# LOA_Legba.net
KiCad netlist of a schematic drawn in EAGLE
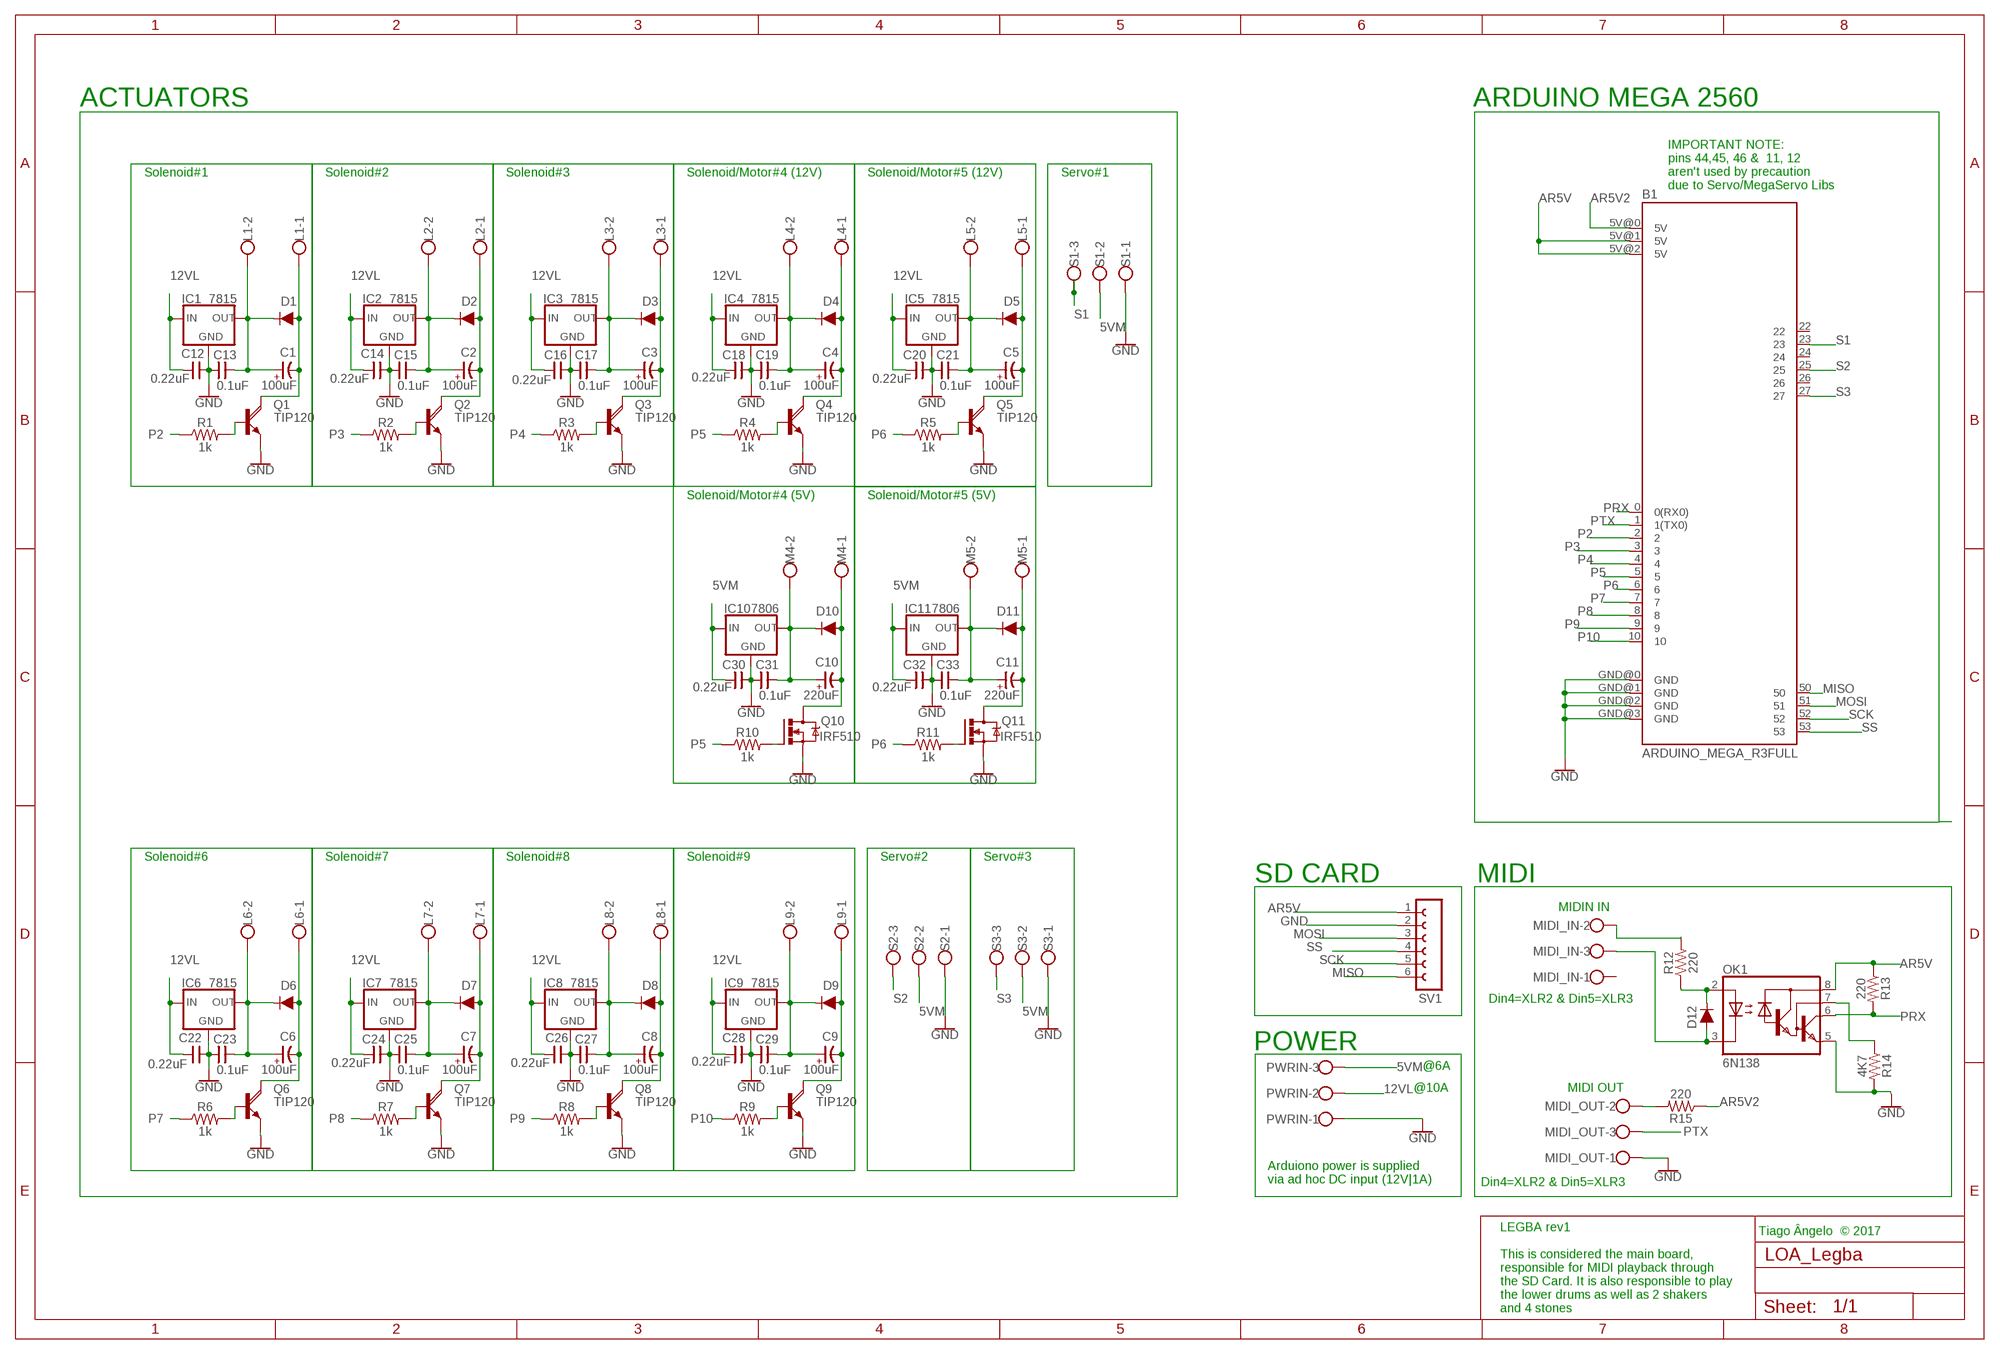
[diagram p0: schematic, sheet 1]

(export (version "E")
  (design (tool "Eeschema 10.0.6"))
  (components
    (comp (ref "B1")
      (value "ARDUINO_MEGA_R3FULL")
      (footprint "eagle-import:ARDUINO_MEGA")
      (libsource (lib "eagle-import") (part "ARDUINO_MEGA_R3FULL"))
    )
    (comp (ref "C1")
      (value "100uF")
      (footprint "eagle-import:CAP-MASTER_E-020X050")
      (libsource (lib "eagle-import") (part "CAP-MASTER_CP-E-020X050"))
    )
    (comp (ref "C2")
      (value "100uF")
      (footprint "eagle-import:CAP-MASTER_E-020X050")
      (libsource (lib "eagle-import") (part "CAP-MASTER_CP-E-020X050"))
    )
    (comp (ref "C3")
      (value "100uF")
      (footprint "eagle-import:CAP-MASTER_E-020X050")
      (libsource (lib "eagle-import") (part "CAP-MASTER_CP-E-020X050"))
    )
    (comp (ref "C4")
      (value "100uF")
      (footprint "eagle-import:CAP-MASTER_E-020X050")
      (libsource (lib "eagle-import") (part "CAP-MASTER_CP-E-020X050"))
    )
    (comp (ref "C5")
      (value "100uF")
      (footprint "eagle-import:CAP-MASTER_E-020X050")
      (libsource (lib "eagle-import") (part "CAP-MASTER_CP-E-020X050"))
    )
    (comp (ref "C6")
      (value "100uF")
      (footprint "eagle-import:CAP-MASTER_E-020X050")
      (libsource (lib "eagle-import") (part "CAP-MASTER_CP-E-020X050"))
    )
    (comp (ref "C7")
      (value "100uF")
      (footprint "eagle-import:CAP-MASTER_E-020X050")
      (libsource (lib "eagle-import") (part "CAP-MASTER_CP-E-020X050"))
    )
    (comp (ref "C8")
      (value "100uF")
      (footprint "eagle-import:CAP-MASTER_E-020X050")
      (libsource (lib "eagle-import") (part "CAP-MASTER_CP-E-020X050"))
    )
    (comp (ref "C9")
      (value "100uF")
      (footprint "eagle-import:CAP-MASTER_E-020X050")
      (libsource (lib "eagle-import") (part "CAP-MASTER_CP-E-020X050"))
    )
    (comp (ref "C10")
      (value "220uF")
      (footprint "eagle-import:E-035X080")
      (libsource (lib "eagle-import") (part "CP-E-035X080"))
    )
    (comp (ref "C11")
      (value "220uF")
      (footprint "eagle-import:E-035X080")
      (libsource (lib "eagle-import") (part "CP-E-035X080"))
    )
    (comp (ref "C12")
      (value "0.22uF")
      (footprint "eagle-import:C025-050X025")
      (libsource (lib "eagle-import") (part "CNP-C025-050X025"))
    )
    (comp (ref "C13")
      (value "0.1uF")
      (footprint "eagle-import:C025-050X025")
      (libsource (lib "eagle-import") (part "CNP-C025-050X025"))
    )
    (comp (ref "C14")
      (value "0.22uF")
      (footprint "eagle-import:C025-050X025")
      (libsource (lib "eagle-import") (part "CNP-C025-050X025"))
    )
    (comp (ref "C15")
      (value "0.1uF")
      (footprint "eagle-import:C025-050X025")
      (libsource (lib "eagle-import") (part "CNP-C025-050X025"))
    )
    (comp (ref "C16")
      (value "0.22uF")
      (footprint "eagle-import:C025-050X025")
      (libsource (lib "eagle-import") (part "CNP-C025-050X025"))
    )
    (comp (ref "C17")
      (value "0.1uF")
      (footprint "eagle-import:C025-050X025")
      (libsource (lib "eagle-import") (part "CNP-C025-050X025"))
    )
    (comp (ref "C18")
      (value "0.22uF")
      (footprint "eagle-import:C025-050X025")
      (libsource (lib "eagle-import") (part "CNP-C025-050X025"))
    )
    (comp (ref "C19")
      (value "0.1uF")
      (footprint "eagle-import:C025-050X025")
      (libsource (lib "eagle-import") (part "CNP-C025-050X025"))
    )
    (comp (ref "C20")
      (value "0.22uF")
      (footprint "eagle-import:C025-050X025")
      (libsource (lib "eagle-import") (part "CNP-C025-050X025"))
    )
    (comp (ref "C21")
      (value "0.1uF")
      (footprint "eagle-import:C025-050X025")
      (libsource (lib "eagle-import") (part "CNP-C025-050X025"))
    )
    (comp (ref "C22")
      (value "0.22uF")
      (footprint "eagle-import:C025-050X025")
      (libsource (lib "eagle-import") (part "CNP-C025-050X025"))
    )
    (comp (ref "C23")
      (value "0.1uF")
      (footprint "eagle-import:C025-050X025")
      (libsource (lib "eagle-import") (part "CNP-C025-050X025"))
    )
    (comp (ref "C24")
      (value "0.22uF")
      (footprint "eagle-import:C025-050X025")
      (libsource (lib "eagle-import") (part "CNP-C025-050X025"))
    )
    (comp (ref "C25")
      (value "0.1uF")
      (footprint "eagle-import:C025-050X025")
      (libsource (lib "eagle-import") (part "CNP-C025-050X025"))
    )
    (comp (ref "C26")
      (value "0.22uF")
      (footprint "eagle-import:C025-050X025")
      (libsource (lib "eagle-import") (part "CNP-C025-050X025"))
    )
    (comp (ref "C27")
      (value "0.1uF")
      (footprint "eagle-import:C025-050X025")
      (libsource (lib "eagle-import") (part "CNP-C025-050X025"))
    )
    (comp (ref "C28")
      (value "0.22uF")
      (footprint "eagle-import:C025-050X025")
      (libsource (lib "eagle-import") (part "CNP-C025-050X025"))
    )
    (comp (ref "C29")
      (value "0.1uF")
      (footprint "eagle-import:C025-050X025")
      (libsource (lib "eagle-import") (part "CNP-C025-050X025"))
    )
    (comp (ref "C30")
      (value "0.22uF")
      (footprint "eagle-import:C025-050X025")
      (libsource (lib "eagle-import") (part "CNP-C025-050X025"))
    )
    (comp (ref "C31")
      (value "0.1uF")
      (footprint "eagle-import:C025-050X025")
      (libsource (lib "eagle-import") (part "CNP-C025-050X025"))
    )
    (comp (ref "C32")
      (value "0.22uF")
      (footprint "eagle-import:C025-050X025")
      (libsource (lib "eagle-import") (part "CNP-C025-050X025"))
    )
    (comp (ref "C33")
      (value "0.1uF")
      (footprint "eagle-import:C025-050X025")
      (libsource (lib "eagle-import") (part "CNP-C025-050X025"))
    )
    (comp (ref "D1")
      (value "1A/50V/1.1V")
      (footprint "eagle-import:DIODE-1N4001-KIT")
      (libsource (lib "eagle-import") (part "DIODE-KIT2"))
    )
    (comp (ref "D2")
      (value "1A/50V/1.1V")
      (footprint "eagle-import:DIODE-1N4001-KIT")
      (libsource (lib "eagle-import") (part "DIODE-KIT2"))
    )
    (comp (ref "D3")
      (value "1A/50V/1.1V")
      (footprint "eagle-import:DIODE-1N4001-KIT")
      (libsource (lib "eagle-import") (part "DIODE-KIT2"))
    )
    (comp (ref "D4")
      (value "1A/50V/1.1V")
      (footprint "eagle-import:DIODE-1N4001-KIT")
      (libsource (lib "eagle-import") (part "DIODE-KIT2"))
    )
    (comp (ref "D5")
      (value "1A/50V/1.1V")
      (footprint "eagle-import:DIODE-1N4001-KIT")
      (libsource (lib "eagle-import") (part "DIODE-KIT2"))
    )
    (comp (ref "D6")
      (value "1A/50V/1.1V")
      (footprint "eagle-import:DIODE-1N4001-KIT")
      (libsource (lib "eagle-import") (part "DIODE-KIT2"))
    )
    (comp (ref "D7")
      (value "1A/50V/1.1V")
      (footprint "eagle-import:DIODE-1N4001-KIT")
      (libsource (lib "eagle-import") (part "DIODE-KIT2"))
    )
    (comp (ref "D8")
      (value "1A/50V/1.1V")
      (footprint "eagle-import:DIODE-1N4001-KIT")
      (libsource (lib "eagle-import") (part "DIODE-KIT2"))
    )
    (comp (ref "D9")
      (value "1A/50V/1.1V")
      (footprint "eagle-import:DIODE-1N4001-KIT")
      (libsource (lib "eagle-import") (part "DIODE-KIT2"))
    )
    (comp (ref "D10")
      (value "1A/50V/1.1V")
      (footprint "eagle-import:DIODE-1N4001-KIT")
      (libsource (lib "eagle-import") (part "DIODE-KIT2"))
    )
    (comp (ref "D11")
      (value "1A/50V/1.1V")
      (footprint "eagle-import:DIODE-1N4001-KIT")
      (libsource (lib "eagle-import") (part "DIODE-KIT2"))
    )
    (comp (ref "D12")
      (value "200mA/100V/1V")
      (footprint "eagle-import:DIODE-1N4148")
      (libsource (lib "eagle-import") (part "DIODE-1N4148"))
    )
    (comp (ref "IC1")
      (value "7815")
      (footprint "eagle-import:78XXS")
      (libsource (lib "eagle-import") (part "78XXS"))
    )
    (comp (ref "IC2")
      (value "7815")
      (footprint "eagle-import:78XXS")
      (libsource (lib "eagle-import") (part "78XXS"))
    )
    (comp (ref "IC3")
      (value "7815")
      (footprint "eagle-import:78XXS")
      (libsource (lib "eagle-import") (part "78XXS"))
    )
    (comp (ref "IC4")
      (value "7815")
      (footprint "eagle-import:78XXS")
      (libsource (lib "eagle-import") (part "78XXS"))
    )
    (comp (ref "IC5")
      (value "7815")
      (footprint "eagle-import:78XXS")
      (libsource (lib "eagle-import") (part "78XXS"))
    )
    (comp (ref "IC6")
      (value "7815")
      (footprint "eagle-import:78XXS")
      (libsource (lib "eagle-import") (part "78XXS"))
    )
    (comp (ref "IC7")
      (value "7815")
      (footprint "eagle-import:78XXS")
      (libsource (lib "eagle-import") (part "78XXS"))
    )
    (comp (ref "IC8")
      (value "7815")
      (footprint "eagle-import:78XXS")
      (libsource (lib "eagle-import") (part "78XXS"))
    )
    (comp (ref "IC9")
      (value "7815")
      (footprint "eagle-import:78XXS")
      (libsource (lib "eagle-import") (part "78XXS"))
    )
    (comp (ref "IC10")
      (value "7806")
      (footprint "eagle-import:78XXS")
      (libsource (lib "eagle-import") (part "78XXS"))
    )
    (comp (ref "IC11")
      (value "7806")
      (footprint "eagle-import:78XXS")
      (libsource (lib "eagle-import") (part "78XXS"))
    )
    (comp (ref "L1")
      (value "W237-102")
      (footprint "eagle-import:W237-102")
      (fields (field (name "MPN") "237-102"))
      (libsource (lib "eagle-import") (part "W237-102"))
    )
    (comp (ref "L2")
      (value "W237-102")
      (footprint "eagle-import:W237-102")
      (fields (field (name "MPN") "237-102"))
      (libsource (lib "eagle-import") (part "W237-102"))
    )
    (comp (ref "L3")
      (value "W237-102")
      (footprint "eagle-import:W237-102")
      (fields (field (name "MPN") "237-102"))
      (libsource (lib "eagle-import") (part "W237-102"))
    )
    (comp (ref "L4")
      (value "W237-102")
      (footprint "eagle-import:W237-102")
      (fields (field (name "MPN") "237-102"))
      (libsource (lib "eagle-import") (part "W237-102"))
    )
    (comp (ref "L5")
      (value "W237-102")
      (footprint "eagle-import:W237-102")
      (fields (field (name "MPN") "237-102"))
      (libsource (lib "eagle-import") (part "W237-102"))
    )
    (comp (ref "L6")
      (value "W237-102")
      (footprint "eagle-import:W237-102")
      (fields (field (name "MPN") "237-102"))
      (libsource (lib "eagle-import") (part "W237-102"))
    )
    (comp (ref "L7")
      (value "W237-102")
      (footprint "eagle-import:W237-102")
      (fields (field (name "MPN") "237-102"))
      (libsource (lib "eagle-import") (part "W237-102"))
    )
    (comp (ref "L8")
      (value "W237-102")
      (footprint "eagle-import:W237-102")
      (fields (field (name "MPN") "237-102"))
      (libsource (lib "eagle-import") (part "W237-102"))
    )
    (comp (ref "L9")
      (value "W237-102")
      (footprint "eagle-import:W237-102")
      (fields (field (name "MPN") "237-102"))
      (libsource (lib "eagle-import") (part "W237-102"))
    )
    (comp (ref "M4")
      (value "W237-102")
      (footprint "eagle-import:W237-102")
      (fields (field (name "MPN") "237-102"))
      (libsource (lib "eagle-import") (part "W237-102"))
    )
    (comp (ref "M5")
      (value "W237-102")
      (footprint "eagle-import:W237-102")
      (fields (field (name "MPN") "237-102"))
      (libsource (lib "eagle-import") (part "W237-102"))
    )
    (comp (ref "MIDI_IN")
      (value "W237-103")
      (footprint "eagle-import:W237-103")
      (fields (field (name "MPN") "237-103"))
      (libsource (lib "eagle-import") (part "W237-103"))
    )
    (comp (ref "MIDI_OUT")
      (value "W237-103")
      (footprint "eagle-import:W237-103")
      (fields (field (name "MPN") "237-103"))
      (libsource (lib "eagle-import") (part "W237-103"))
    )
    (comp (ref "OK1")
      (value "6N138")
      (footprint "eagle-import:DIL08")
      (fields (field (name "MF") "VISHAY/TELEFUNKEN"))
      (libsource (lib "eagle-import") (part "6N138"))
    )
    (comp (ref "PWRIN")
      (value "W237-103")
      (footprint "eagle-import:W237-103")
      (fields (field (name "MPN") "237-103"))
      (libsource (lib "eagle-import") (part "W237-103"))
    )
    (comp (ref "Q1")
      (value "TIP120")
      (footprint "eagle-import:ROCKETFARM_TO220AV")
      (libsource (lib "eagle-import") (part "ROCKETFARM_TIP120V"))
    )
    (comp (ref "Q2")
      (value "TIP120")
      (footprint "eagle-import:ROCKETFARM_TO220AV")
      (libsource (lib "eagle-import") (part "ROCKETFARM_TIP120V"))
    )
    (comp (ref "Q3")
      (value "TIP120")
      (footprint "eagle-import:ROCKETFARM_TO220AV")
      (libsource (lib "eagle-import") (part "ROCKETFARM_TIP120V"))
    )
    (comp (ref "Q4")
      (value "TIP120")
      (footprint "eagle-import:ROCKETFARM_TO220AV")
      (libsource (lib "eagle-import") (part "ROCKETFARM_TIP120V"))
    )
    (comp (ref "Q5")
      (value "TIP120")
      (footprint "eagle-import:ROCKETFARM_TO220AV")
      (libsource (lib "eagle-import") (part "ROCKETFARM_TIP120V"))
    )
    (comp (ref "Q6")
      (value "TIP120")
      (footprint "eagle-import:ROCKETFARM_TO220AV")
      (libsource (lib "eagle-import") (part "ROCKETFARM_TIP120V"))
    )
    (comp (ref "Q7")
      (value "TIP120")
      (footprint "eagle-import:ROCKETFARM_TO220AV")
      (libsource (lib "eagle-import") (part "ROCKETFARM_TIP120V"))
    )
    (comp (ref "Q8")
      (value "TIP120")
      (footprint "eagle-import:ROCKETFARM_TO220AV")
      (libsource (lib "eagle-import") (part "ROCKETFARM_TIP120V"))
    )
    (comp (ref "Q9")
      (value "TIP120")
      (footprint "eagle-import:ROCKETFARM_TO220AV")
      (libsource (lib "eagle-import") (part "ROCKETFARM_TIP120V"))
    )
    (comp (ref "Q10")
      (value "IRF510")
      (footprint "eagle-import:TO220BV")
      (libsource (lib "eagle-import") (part "IRF520"))
    )
    (comp (ref "Q11")
      (value "IRF510")
      (footprint "eagle-import:TO220BV")
      (libsource (lib "eagle-import") (part "IRF520"))
    )
    (comp (ref "R1")
      (value "1k")
      (footprint "eagle-import:AXIAL-0.1")
      (libsource (lib "eagle-import") (part "1KOHM-VERT-1/4W-1%"))
    )
    (comp (ref "R2")
      (value "1k")
      (footprint "eagle-import:AXIAL-0.1")
      (libsource (lib "eagle-import") (part "1KOHM-VERT-1/4W-1%"))
    )
    (comp (ref "R3")
      (value "1k")
      (footprint "eagle-import:AXIAL-0.1")
      (libsource (lib "eagle-import") (part "1KOHM-VERT-1/4W-1%"))
    )
    (comp (ref "R4")
      (value "1k")
      (footprint "eagle-import:AXIAL-0.1")
      (libsource (lib "eagle-import") (part "1KOHM-VERT-1/4W-1%"))
    )
    (comp (ref "R5")
      (value "1k")
      (footprint "eagle-import:AXIAL-0.1")
      (libsource (lib "eagle-import") (part "1KOHM-VERT-1/4W-1%"))
    )
    (comp (ref "R6")
      (value "1k")
      (footprint "eagle-import:AXIAL-0.1")
      (libsource (lib "eagle-import") (part "1KOHM-VERT-1/4W-1%"))
    )
    (comp (ref "R7")
      (value "1k")
      (footprint "eagle-import:AXIAL-0.1")
      (libsource (lib "eagle-import") (part "1KOHM-VERT-1/4W-1%"))
    )
    (comp (ref "R8")
      (value "1k")
      (footprint "eagle-import:AXIAL-0.1")
      (libsource (lib "eagle-import") (part "1KOHM-VERT-1/4W-1%"))
    )
    (comp (ref "R9")
      (value "1k")
      (footprint "eagle-import:AXIAL-0.1")
      (libsource (lib "eagle-import") (part "1KOHM-VERT-1/4W-1%"))
    )
    (comp (ref "R10")
      (value "1k")
      (footprint "eagle-import:AXIAL-0.1")
      (libsource (lib "eagle-import") (part "1KOHM-VERT-1/4W-1%"))
    )
    (comp (ref "R11")
      (value "1k")
      (footprint "eagle-import:AXIAL-0.1")
      (libsource (lib "eagle-import") (part "1KOHM-VERT-1/4W-1%"))
    )
    (comp (ref "R12")
      (value "220")
      (footprint "eagle-import:AXIAL-0.3")
      (libsource (lib "eagle-import") (part "1KOHM-HORIZ-1/4W-5%"))
    )
    (comp (ref "R13")
      (value "220")
      (footprint "eagle-import:AXIAL-0.3")
      (libsource (lib "eagle-import") (part "1KOHM-HORIZ-1/4W-5%"))
    )
    (comp (ref "R14")
      (value "4K7")
      (footprint "eagle-import:AXIAL-0.3")
      (libsource (lib "eagle-import") (part "1KOHM-HORIZ-1/4W-5%"))
    )
    (comp (ref "R15")
      (value "220")
      (footprint "eagle-import:AXIAL-0.3")
      (libsource (lib "eagle-import") (part "1KOHM-HORIZ-1/4W-5%"))
    )
    (comp (ref "S1")
      (value "W237-103")
      (footprint "eagle-import:W237-103")
      (fields (field (name "MPN") "237-103"))
      (libsource (lib "eagle-import") (part "W237-103"))
    )
    (comp (ref "S2")
      (value "W237-103")
      (footprint "eagle-import:W237-103")
      (fields (field (name "MPN") "237-103"))
      (libsource (lib "eagle-import") (part "W237-103"))
    )
    (comp (ref "S3")
      (value "W237-103")
      (footprint "eagle-import:W237-103")
      (fields (field (name "MPN") "237-103"))
      (libsource (lib "eagle-import") (part "W237-103"))
    )
    (comp (ref "SV1")
      (value "FE06W")
      (footprint "eagle-import:FE06W")
      (libsource (lib "eagle-import") (part "FE06W"))
    )
  )
  (nets
    (net (code "1") (name "/5VM") (class "Default")
      (node (ref "C30") (pin "1") (pinfunction "1_1") (pintype "passive"))
      (node (ref "C32") (pin "1") (pinfunction "1_1") (pintype "passive"))
      (node (ref "IC10") (pin "IN") (pinfunction "IN_IN") (pintype "input"))
      (node (ref "IC11") (pin "IN") (pinfunction "IN_IN") (pintype "input"))
      (node (ref "PWRIN") (pin "3") (pinfunction "KL_3") (pintype "passive"))
      (node (ref "S1") (pin "2") (pinfunction "KL_2") (pintype "passive"))
      (node (ref "S2") (pin "2") (pinfunction "KL_2") (pintype "passive"))
      (node (ref "S3") (pin "2") (pinfunction "KL_2") (pintype "passive"))
    )
    (net (code "2") (name "/12VL") (class "Default")
      (node (ref "C12") (pin "1") (pinfunction "1_1") (pintype "passive"))
      (node (ref "C14") (pin "1") (pinfunction "1_1") (pintype "passive"))
      (node (ref "C16") (pin "1") (pinfunction "1_1") (pintype "passive"))
      (node (ref "C18") (pin "1") (pinfunction "1_1") (pintype "passive"))
      (node (ref "C20") (pin "1") (pinfunction "1_1") (pintype "passive"))
      (node (ref "C22") (pin "1") (pinfunction "1_1") (pintype "passive"))
      (node (ref "C24") (pin "1") (pinfunction "1_1") (pintype "passive"))
      (node (ref "C26") (pin "1") (pinfunction "1_1") (pintype "passive"))
      (node (ref "C28") (pin "1") (pinfunction "1_1") (pintype "passive"))
      (node (ref "IC1") (pin "IN") (pinfunction "IN_IN") (pintype "input"))
      (node (ref "IC2") (pin "IN") (pinfunction "IN_IN") (pintype "input"))
      (node (ref "IC3") (pin "IN") (pinfunction "IN_IN") (pintype "input"))
      (node (ref "IC4") (pin "IN") (pinfunction "IN_IN") (pintype "input"))
      (node (ref "IC5") (pin "IN") (pinfunction "IN_IN") (pintype "input"))
      (node (ref "IC6") (pin "IN") (pinfunction "IN_IN") (pintype "input"))
      (node (ref "IC7") (pin "IN") (pinfunction "IN_IN") (pintype "input"))
      (node (ref "IC8") (pin "IN") (pinfunction "IN_IN") (pintype "input"))
      (node (ref "IC9") (pin "IN") (pinfunction "IN_IN") (pintype "input"))
      (node (ref "PWRIN") (pin "2") (pinfunction "KL_2") (pintype "passive"))
    )
    (net (code "3") (name "/AR5V") (class "Default")
      (node (ref "B1") (pin "5V@1") (pinfunction "5V_5V@1") (pintype "bidirectional"))
      (node (ref "B1") (pin "5V@2") (pinfunction "5V_5V@2") (pintype "bidirectional"))
      (node (ref "OK1") (pin "8") (pinfunction "VCC_8") (pintype "passive"))
      (node (ref "R13") (pin "P$1") (pinfunction "1_P$1") (pintype "passive"))
      (node (ref "SV1") (pin "1") (pinfunction "1_1") (pintype "passive"))
    )
    (net (code "4") (name "/AR5V2") (class "Default")
      (node (ref "B1") (pin "5V@0") (pinfunction "5V_5V@0") (pintype "bidirectional"))
      (node (ref "R15") (pin "P$1") (pinfunction "1_P$1") (pintype "passive"))
    )
    (net (code "5") (name "/MISO") (class "Default")
      (node (ref "B1") (pin "50") (pinfunction "50_50") (pintype "bidirectional"))
      (node (ref "SV1") (pin "6") (pinfunction "6_6") (pintype "passive"))
    )
    (net (code "6") (name "/MOSI") (class "Default")
      (node (ref "B1") (pin "51") (pinfunction "51_51") (pintype "bidirectional"))
      (node (ref "SV1") (pin "3") (pinfunction "3_3") (pintype "passive"))
    )
    (net (code "7") (name "/P2") (class "Default")
      (node (ref "B1") (pin "2") (pinfunction "2_2") (pintype "bidirectional"))
      (node (ref "R1") (pin "P$1") (pinfunction "1_P$1") (pintype "passive"))
    )
    (net (code "8") (name "/P3") (class "Default")
      (node (ref "B1") (pin "3") (pinfunction "3_3") (pintype "bidirectional"))
      (node (ref "R2") (pin "P$1") (pinfunction "1_P$1") (pintype "passive"))
    )
    (net (code "9") (name "/P4") (class "Default")
      (node (ref "B1") (pin "4") (pinfunction "4_4") (pintype "bidirectional"))
      (node (ref "R3") (pin "P$1") (pinfunction "1_P$1") (pintype "passive"))
    )
    (net (code "10") (name "/P5") (class "Default")
      (node (ref "B1") (pin "5") (pinfunction "5_5") (pintype "bidirectional"))
      (node (ref "R10") (pin "P$1") (pinfunction "1_P$1") (pintype "passive"))
      (node (ref "R4") (pin "P$1") (pinfunction "1_P$1") (pintype "passive"))
    )
    (net (code "11") (name "/P6") (class "Default")
      (node (ref "B1") (pin "6") (pinfunction "6_6") (pintype "bidirectional"))
      (node (ref "R11") (pin "P$1") (pinfunction "1_P$1") (pintype "passive"))
      (node (ref "R5") (pin "P$1") (pinfunction "1_P$1") (pintype "passive"))
    )
    (net (code "12") (name "/P7") (class "Default")
      (node (ref "B1") (pin "7") (pinfunction "7_7") (pintype "bidirectional"))
      (node (ref "R6") (pin "P$1") (pinfunction "1_P$1") (pintype "passive"))
    )
    (net (code "13") (name "/P8") (class "Default")
      (node (ref "B1") (pin "8") (pinfunction "8_8") (pintype "bidirectional"))
      (node (ref "R7") (pin "P$1") (pinfunction "1_P$1") (pintype "passive"))
    )
    (net (code "14") (name "/P9") (class "Default")
      (node (ref "B1") (pin "9") (pinfunction "9_9") (pintype "bidirectional"))
      (node (ref "R8") (pin "P$1") (pinfunction "1_P$1") (pintype "passive"))
    )
    (net (code "15") (name "/P10") (class "Default")
      (node (ref "B1") (pin "10") (pinfunction "10_10") (pintype "bidirectional"))
      (node (ref "R9") (pin "P$1") (pinfunction "1_P$1") (pintype "passive"))
    )
    (net (code "16") (name "/PRX") (class "Default")
      (node (ref "B1") (pin "0") (pinfunction "0(RX0)_0") (pintype "bidirectional"))
      (node (ref "OK1") (pin "6") (pinfunction "VO_6") (pintype "passive"))
      (node (ref "R13") (pin "P$2") (pinfunction "2_P$2") (pintype "passive"))
    )
    (net (code "17") (name "/PTX") (class "Default")
      (node (ref "B1") (pin "1") (pinfunction "1(TX0)_1") (pintype "bidirectional"))
      (node (ref "MIDI_OUT") (pin "3") (pinfunction "KL_3") (pintype "passive"))
    )
    (net (code "18") (name "/S1") (class "Default")
      (node (ref "B1") (pin "23") (pinfunction "23_23") (pintype "bidirectional"))
      (node (ref "S1") (pin "3") (pinfunction "KL_3") (pintype "passive"))
    )
    (net (code "19") (name "/S2") (class "Default")
      (node (ref "B1") (pin "25") (pinfunction "25_25") (pintype "bidirectional"))
      (node (ref "S2") (pin "3") (pinfunction "KL_3") (pintype "passive"))
    )
    (net (code "20") (name "/S3") (class "Default")
      (node (ref "B1") (pin "27") (pinfunction "27_27") (pintype "bidirectional"))
      (node (ref "S3") (pin "3") (pinfunction "KL_3") (pintype "passive"))
    )
    (net (code "21") (name "/SCK") (class "Default")
      (node (ref "B1") (pin "52") (pinfunction "52_52") (pintype "bidirectional"))
      (node (ref "SV1") (pin "5") (pinfunction "5_5") (pintype "passive"))
    )
    (net (code "22") (name "/SS") (class "Default")
      (node (ref "B1") (pin "53") (pinfunction "53_53") (pintype "bidirectional"))
      (node (ref "SV1") (pin "4") (pinfunction "4_4") (pintype "passive"))
    )
    (net (code "23") (name "GND") (class "Default")
      (node (ref "B1") (pin "GND@0") (pinfunction "GND_GND@0") (pintype "bidirectional"))
      (node (ref "B1") (pin "GND@1") (pinfunction "GND_GND@1") (pintype "bidirectional"))
      (node (ref "B1") (pin "GND@2") (pinfunction "GND_GND@2") (pintype "bidirectional"))
      (node (ref "B1") (pin "GND@3") (pinfunction "GND_GND@3") (pintype "bidirectional"))
      (node (ref "C12") (pin "2") (pinfunction "2_2") (pintype "passive"))
      (node (ref "C13") (pin "1") (pinfunction "1_1") (pintype "passive"))
      (node (ref "C14") (pin "2") (pinfunction "2_2") (pintype "passive"))
      (node (ref "C15") (pin "1") (pinfunction "1_1") (pintype "passive"))
      (node (ref "C16") (pin "2") (pinfunction "2_2") (pintype "passive"))
      (node (ref "C17") (pin "1") (pinfunction "1_1") (pintype "passive"))
      (node (ref "C18") (pin "2") (pinfunction "2_2") (pintype "passive"))
      (node (ref "C19") (pin "1") (pinfunction "1_1") (pintype "passive"))
      (node (ref "C20") (pin "2") (pinfunction "2_2") (pintype "passive"))
      (node (ref "C21") (pin "1") (pinfunction "1_1") (pintype "passive"))
      (node (ref "C22") (pin "2") (pinfunction "2_2") (pintype "passive"))
      (node (ref "C23") (pin "1") (pinfunction "1_1") (pintype "passive"))
      (node (ref "C24") (pin "2") (pinfunction "2_2") (pintype "passive"))
      (node (ref "C25") (pin "1") (pinfunction "1_1") (pintype "passive"))
      (node (ref "C26") (pin "2") (pinfunction "2_2") (pintype "passive"))
      (node (ref "C27") (pin "1") (pinfunction "1_1") (pintype "passive"))
      (node (ref "C28") (pin "2") (pinfunction "2_2") (pintype "passive"))
      (node (ref "C29") (pin "1") (pinfunction "1_1") (pintype "passive"))
      (node (ref "C30") (pin "2") (pinfunction "2_2") (pintype "passive"))
      (node (ref "C31") (pin "1") (pinfunction "1_1") (pintype "passive"))
      (node (ref "C32") (pin "2") (pinfunction "2_2") (pintype "passive"))
      (node (ref "C33") (pin "1") (pinfunction "1_1") (pintype "passive"))
      (node (ref "IC1") (pin "GND") (pinfunction "GND_GND") (pintype "input"))
      (node (ref "IC10") (pin "GND") (pinfunction "GND_GND") (pintype "input"))
      (node (ref "IC11") (pin "GND") (pinfunction "GND_GND") (pintype "input"))
      (node (ref "IC2") (pin "GND") (pinfunction "GND_GND") (pintype "input"))
      (node (ref "IC3") (pin "GND") (pinfunction "GND_GND") (pintype "input"))
      (node (ref "IC4") (pin "GND") (pinfunction "GND_GND") (pintype "input"))
      (node (ref "IC5") (pin "GND") (pinfunction "GND_GND") (pintype "input"))
      (node (ref "IC6") (pin "GND") (pinfunction "GND_GND") (pintype "input"))
      (node (ref "IC7") (pin "GND") (pinfunction "GND_GND") (pintype "input"))
      (node (ref "IC8") (pin "GND") (pinfunction "GND_GND") (pintype "input"))
      (node (ref "IC9") (pin "GND") (pinfunction "GND_GND") (pintype "input"))
      (node (ref "MIDI_OUT") (pin "1") (pinfunction "KL_1") (pintype "passive"))
      (node (ref "OK1") (pin "5") (pinfunction "GND_5") (pintype "passive"))
      (node (ref "PWRIN") (pin "1") (pinfunction "KL_1") (pintype "passive"))
      (node (ref "Q1") (pin "E") (pinfunction "E_E") (pintype "passive"))
      (node (ref "Q10") (pin "S") (pinfunction "S_S") (pintype "passive"))
      (node (ref "Q11") (pin "S") (pinfunction "S_S") (pintype "passive"))
      (node (ref "Q2") (pin "E") (pinfunction "E_E") (pintype "passive"))
      (node (ref "Q3") (pin "E") (pinfunction "E_E") (pintype "passive"))
      (node (ref "Q4") (pin "E") (pinfunction "E_E") (pintype "passive"))
      (node (ref "Q5") (pin "E") (pinfunction "E_E") (pintype "passive"))
      (node (ref "Q6") (pin "E") (pinfunction "E_E") (pintype "passive"))
      (node (ref "Q7") (pin "E") (pinfunction "E_E") (pintype "passive"))
      (node (ref "Q8") (pin "E") (pinfunction "E_E") (pintype "passive"))
      (node (ref "Q9") (pin "E") (pinfunction "E_E") (pintype "passive"))
      (node (ref "R14") (pin "P$2") (pinfunction "2_P$2") (pintype "passive"))
      (node (ref "S1") (pin "1") (pinfunction "KL_1") (pintype "passive"))
      (node (ref "S2") (pin "1") (pinfunction "KL_1") (pintype "passive"))
      (node (ref "S3") (pin "1") (pinfunction "KL_1") (pintype "passive"))
      (node (ref "SV1") (pin "2") (pinfunction "2_2") (pintype "passive"))
    )
    (net (code "24") (name "Net-(L1A-KL)") (class "Default")
      (node (ref "C1") (pin "-") (pinfunction "-_-") (pintype "passive"))
      (node (ref "D1") (pin "A") (pinfunction "A_A") (pintype "passive"))
      (node (ref "L1") (pin "1") (pinfunction "KL_1") (pintype "passive"))
      (node (ref "Q1") (pin "C") (pinfunction "C_C") (pintype "passive"))
    )
    (net (code "25") (name "Net-(L1B-KL)") (class "Default")
      (node (ref "C1") (pin "+") (pinfunction "+_+") (pintype "passive"))
      (node (ref "C13") (pin "2") (pinfunction "2_2") (pintype "passive"))
      (node (ref "D1") (pin "C") (pinfunction "C_C") (pintype "passive"))
      (node (ref "IC1") (pin "OUT") (pinfunction "OUT_OUT") (pintype "passive"))
      (node (ref "L1") (pin "2") (pinfunction "KL_2") (pintype "passive"))
    )
    (net (code "26") (name "Net-(L2A-KL)") (class "Default")
      (node (ref "C2") (pin "-") (pinfunction "-_-") (pintype "passive"))
      (node (ref "D2") (pin "A") (pinfunction "A_A") (pintype "passive"))
      (node (ref "L2") (pin "1") (pinfunction "KL_1") (pintype "passive"))
      (node (ref "Q2") (pin "C") (pinfunction "C_C") (pintype "passive"))
    )
    (net (code "27") (name "Net-(L2B-KL)") (class "Default")
      (node (ref "C15") (pin "2") (pinfunction "2_2") (pintype "passive"))
      (node (ref "C2") (pin "+") (pinfunction "+_+") (pintype "passive"))
      (node (ref "D2") (pin "C") (pinfunction "C_C") (pintype "passive"))
      (node (ref "IC2") (pin "OUT") (pinfunction "OUT_OUT") (pintype "passive"))
      (node (ref "L2") (pin "2") (pinfunction "KL_2") (pintype "passive"))
    )
    (net (code "28") (name "Net-(L3A-KL)") (class "Default")
      (node (ref "C3") (pin "-") (pinfunction "-_-") (pintype "passive"))
      (node (ref "D3") (pin "A") (pinfunction "A_A") (pintype "passive"))
      (node (ref "L3") (pin "1") (pinfunction "KL_1") (pintype "passive"))
      (node (ref "Q3") (pin "C") (pinfunction "C_C") (pintype "passive"))
    )
    (net (code "29") (name "Net-(L3B-KL)") (class "Default")
      (node (ref "C17") (pin "2") (pinfunction "2_2") (pintype "passive"))
      (node (ref "C3") (pin "+") (pinfunction "+_+") (pintype "passive"))
      (node (ref "D3") (pin "C") (pinfunction "C_C") (pintype "passive"))
      (node (ref "IC3") (pin "OUT") (pinfunction "OUT_OUT") (pintype "passive"))
      (node (ref "L3") (pin "2") (pinfunction "KL_2") (pintype "passive"))
    )
    (net (code "30") (name "Net-(L4A-KL)") (class "Default")
      (node (ref "C4") (pin "-") (pinfunction "-_-") (pintype "passive"))
      (node (ref "D4") (pin "A") (pinfunction "A_A") (pintype "passive"))
      (node (ref "L4") (pin "1") (pinfunction "KL_1") (pintype "passive"))
      (node (ref "Q4") (pin "C") (pinfunction "C_C") (pintype "passive"))
    )
    (net (code "31") (name "Net-(L4B-KL)") (class "Default")
      (node (ref "C19") (pin "2") (pinfunction "2_2") (pintype "passive"))
      (node (ref "C4") (pin "+") (pinfunction "+_+") (pintype "passive"))
      (node (ref "D4") (pin "C") (pinfunction "C_C") (pintype "passive"))
      (node (ref "IC4") (pin "OUT") (pinfunction "OUT_OUT") (pintype "passive"))
      (node (ref "L4") (pin "2") (pinfunction "KL_2") (pintype "passive"))
    )
    (net (code "32") (name "Net-(L5A-KL)") (class "Default")
      (node (ref "C5") (pin "-") (pinfunction "-_-") (pintype "passive"))
      (node (ref "D5") (pin "A") (pinfunction "A_A") (pintype "passive"))
      (node (ref "L5") (pin "1") (pinfunction "KL_1") (pintype "passive"))
      (node (ref "Q5") (pin "C") (pinfunction "C_C") (pintype "passive"))
    )
    (net (code "33") (name "Net-(L5B-KL)") (class "Default")
      (node (ref "C21") (pin "2") (pinfunction "2_2") (pintype "passive"))
      (node (ref "C5") (pin "+") (pinfunction "+_+") (pintype "passive"))
      (node (ref "D5") (pin "C") (pinfunction "C_C") (pintype "passive"))
      (node (ref "IC5") (pin "OUT") (pinfunction "OUT_OUT") (pintype "passive"))
      (node (ref "L5") (pin "2") (pinfunction "KL_2") (pintype "passive"))
    )
    (net (code "34") (name "Net-(L6A-KL)") (class "Default")
      (node (ref "C6") (pin "-") (pinfunction "-_-") (pintype "passive"))
      (node (ref "D6") (pin "A") (pinfunction "A_A") (pintype "passive"))
      (node (ref "L6") (pin "1") (pinfunction "KL_1") (pintype "passive"))
      (node (ref "Q6") (pin "C") (pinfunction "C_C") (pintype "passive"))
    )
    (net (code "35") (name "Net-(L6B-KL)") (class "Default")
      (node (ref "C23") (pin "2") (pinfunction "2_2") (pintype "passive"))
      (node (ref "C6") (pin "+") (pinfunction "+_+") (pintype "passive"))
      (node (ref "D6") (pin "C") (pinfunction "C_C") (pintype "passive"))
      (node (ref "IC6") (pin "OUT") (pinfunction "OUT_OUT") (pintype "passive"))
      (node (ref "L6") (pin "2") (pinfunction "KL_2") (pintype "passive"))
    )
    (net (code "36") (name "Net-(L7A-KL)") (class "Default")
      (node (ref "C7") (pin "-") (pinfunction "-_-") (pintype "passive"))
      (node (ref "D7") (pin "A") (pinfunction "A_A") (pintype "passive"))
      (node (ref "L7") (pin "1") (pinfunction "KL_1") (pintype "passive"))
      (node (ref "Q7") (pin "C") (pinfunction "C_C") (pintype "passive"))
    )
    (net (code "37") (name "Net-(L7B-KL)") (class "Default")
      (node (ref "C25") (pin "2") (pinfunction "2_2") (pintype "passive"))
      (node (ref "C7") (pin "+") (pinfunction "+_+") (pintype "passive"))
      (node (ref "D7") (pin "C") (pinfunction "C_C") (pintype "passive"))
      (node (ref "IC7") (pin "OUT") (pinfunction "OUT_OUT") (pintype "passive"))
      (node (ref "L7") (pin "2") (pinfunction "KL_2") (pintype "passive"))
    )
    (net (code "38") (name "Net-(L8A-KL)") (class "Default")
      (node (ref "C8") (pin "-") (pinfunction "-_-") (pintype "passive"))
      (node (ref "D8") (pin "A") (pinfunction "A_A") (pintype "passive"))
      (node (ref "L8") (pin "1") (pinfunction "KL_1") (pintype "passive"))
      (node (ref "Q8") (pin "C") (pinfunction "C_C") (pintype "passive"))
    )
    (net (code "39") (name "Net-(L8B-KL)") (class "Default")
      (node (ref "C27") (pin "2") (pinfunction "2_2") (pintype "passive"))
      (node (ref "C8") (pin "+") (pinfunction "+_+") (pintype "passive"))
      (node (ref "D8") (pin "C") (pinfunction "C_C") (pintype "passive"))
      (node (ref "IC8") (pin "OUT") (pinfunction "OUT_OUT") (pintype "passive"))
      (node (ref "L8") (pin "2") (pinfunction "KL_2") (pintype "passive"))
    )
    (net (code "40") (name "Net-(L9A-KL)") (class "Default")
      (node (ref "C9") (pin "-") (pinfunction "-_-") (pintype "passive"))
      (node (ref "D9") (pin "A") (pinfunction "A_A") (pintype "passive"))
      (node (ref "L9") (pin "1") (pinfunction "KL_1") (pintype "passive"))
      (node (ref "Q9") (pin "C") (pinfunction "C_C") (pintype "passive"))
    )
    (net (code "41") (name "Net-(L9B-KL)") (class "Default")
      (node (ref "C29") (pin "2") (pinfunction "2_2") (pintype "passive"))
      (node (ref "C9") (pin "+") (pinfunction "+_+") (pintype "passive"))
      (node (ref "D9") (pin "C") (pinfunction "C_C") (pintype "passive"))
      (node (ref "IC9") (pin "OUT") (pinfunction "OUT_OUT") (pintype "passive"))
      (node (ref "L9") (pin "2") (pinfunction "KL_2") (pintype "passive"))
    )
    (net (code "42") (name "Net-(M4A-KL)") (class "Default")
      (node (ref "C10") (pin "-") (pinfunction "-_-") (pintype "passive"))
      (node (ref "D10") (pin "A") (pinfunction "A_A") (pintype "passive"))
      (node (ref "M4") (pin "1") (pinfunction "KL_1") (pintype "passive"))
      (node (ref "Q10") (pin "D") (pinfunction "D_D") (pintype "passive"))
    )
    (net (code "43") (name "Net-(M4B-KL)") (class "Default")
      (node (ref "C10") (pin "+") (pinfunction "+_+") (pintype "passive"))
      (node (ref "C31") (pin "2") (pinfunction "2_2") (pintype "passive"))
      (node (ref "D10") (pin "C") (pinfunction "C_C") (pintype "passive"))
      (node (ref "IC10") (pin "OUT") (pinfunction "OUT_OUT") (pintype "passive"))
      (node (ref "M4") (pin "2") (pinfunction "KL_2") (pintype "passive"))
    )
    (net (code "44") (name "Net-(M5A-KL)") (class "Default")
      (node (ref "C11") (pin "-") (pinfunction "-_-") (pintype "passive"))
      (node (ref "D11") (pin "A") (pinfunction "A_A") (pintype "passive"))
      (node (ref "M5") (pin "1") (pinfunction "KL_1") (pintype "passive"))
      (node (ref "Q11") (pin "D") (pinfunction "D_D") (pintype "passive"))
    )
    (net (code "45") (name "Net-(M5B-KL)") (class "Default")
      (node (ref "C11") (pin "+") (pinfunction "+_+") (pintype "passive"))
      (node (ref "C33") (pin "2") (pinfunction "2_2") (pintype "passive"))
      (node (ref "D11") (pin "C") (pinfunction "C_C") (pintype "passive"))
      (node (ref "IC11") (pin "OUT") (pinfunction "OUT_OUT") (pintype "passive"))
      (node (ref "M5") (pin "2") (pinfunction "KL_2") (pintype "passive"))
    )
    (net (code "46") (name "Net-(MIDI_INB-KL)") (class "Default")
      (node (ref "MIDI_IN") (pin "2") (pinfunction "KL_2") (pintype "passive"))
      (node (ref "R12") (pin "P$2") (pinfunction "2_P$2") (pintype "passive"))
    )
    (net (code "47") (name "Net-(MIDI_INC-KL)") (class "Default")
      (node (ref "D12") (pin "A") (pinfunction "A_A") (pintype "passive"))
      (node (ref "MIDI_IN") (pin "3") (pinfunction "KL_3") (pintype "passive"))
      (node (ref "OK1") (pin "3") (pinfunction "C_3") (pintype "passive"))
    )
    (net (code "48") (name "Net-(MIDI_OUTB-KL)") (class "Default")
      (node (ref "MIDI_OUT") (pin "2") (pinfunction "KL_2") (pintype "passive"))
      (node (ref "R15") (pin "P$2") (pinfunction "2_P$2") (pintype "passive"))
    )
    (net (code "49") (name "Net-(OK1-A)") (class "Default")
      (node (ref "D12") (pin "C") (pinfunction "C_C") (pintype "passive"))
      (node (ref "OK1") (pin "2") (pinfunction "A_2") (pintype "passive"))
      (node (ref "R12") (pin "P$1") (pinfunction "1_P$1") (pintype "passive"))
    )
    (net (code "50") (name "Net-(OK1-VB)") (class "Default")
      (node (ref "OK1") (pin "7") (pinfunction "VB_7") (pintype "passive"))
      (node (ref "R14") (pin "P$1") (pinfunction "1_P$1") (pintype "passive"))
    )
    (net (code "51") (name "Net-(R1-2)") (class "Default")
      (node (ref "Q1") (pin "B") (pinfunction "B_B") (pintype "passive"))
      (node (ref "R1") (pin "P$2") (pinfunction "2_P$2") (pintype "passive"))
    )
    (net (code "52") (name "Net-(R2-2)") (class "Default")
      (node (ref "Q2") (pin "B") (pinfunction "B_B") (pintype "passive"))
      (node (ref "R2") (pin "P$2") (pinfunction "2_P$2") (pintype "passive"))
    )
    (net (code "53") (name "Net-(R3-2)") (class "Default")
      (node (ref "Q3") (pin "B") (pinfunction "B_B") (pintype "passive"))
      (node (ref "R3") (pin "P$2") (pinfunction "2_P$2") (pintype "passive"))
    )
    (net (code "54") (name "Net-(R4-2)") (class "Default")
      (node (ref "Q4") (pin "B") (pinfunction "B_B") (pintype "passive"))
      (node (ref "R4") (pin "P$2") (pinfunction "2_P$2") (pintype "passive"))
    )
    (net (code "55") (name "Net-(R5-2)") (class "Default")
      (node (ref "Q5") (pin "B") (pinfunction "B_B") (pintype "passive"))
      (node (ref "R5") (pin "P$2") (pinfunction "2_P$2") (pintype "passive"))
    )
    (net (code "56") (name "Net-(R6-2)") (class "Default")
      (node (ref "Q6") (pin "B") (pinfunction "B_B") (pintype "passive"))
      (node (ref "R6") (pin "P$2") (pinfunction "2_P$2") (pintype "passive"))
    )
    (net (code "57") (name "Net-(R7-2)") (class "Default")
      (node (ref "Q7") (pin "B") (pinfunction "B_B") (pintype "passive"))
      (node (ref "R7") (pin "P$2") (pinfunction "2_P$2") (pintype "passive"))
    )
    (net (code "58") (name "Net-(R8-2)") (class "Default")
      (node (ref "Q8") (pin "B") (pinfunction "B_B") (pintype "passive"))
      (node (ref "R8") (pin "P$2") (pinfunction "2_P$2") (pintype "passive"))
    )
    (net (code "59") (name "Net-(R9-2)") (class "Default")
      (node (ref "Q9") (pin "B") (pinfunction "B_B") (pintype "passive"))
      (node (ref "R9") (pin "P$2") (pinfunction "2_P$2") (pintype "passive"))
    )
    (net (code "60") (name "Net-(R10-2)") (class "Default")
      (node (ref "Q10") (pin "G") (pinfunction "G_G") (pintype "passive"))
      (node (ref "R10") (pin "P$2") (pinfunction "2_P$2") (pintype "passive"))
    )
    (net (code "61") (name "Net-(R11-2)") (class "Default")
      (node (ref "Q11") (pin "G") (pinfunction "G_G") (pintype "passive"))
      (node (ref "R11") (pin "P$2") (pinfunction "2_P$2") (pintype "passive"))
    )
    (net (code "62") (name "unconnected-(B1-Pad22)") (class "Default")
      (node (ref "B1") (pin "22") (pinfunction "22_22") (pintype "bidirectional"))
    )
    (net (code "63") (name "unconnected-(B1-Pad24)") (class "Default")
      (node (ref "B1") (pin "24") (pinfunction "24_24") (pintype "bidirectional"))
    )
    (net (code "64") (name "unconnected-(B1-Pad26)") (class "Default")
      (node (ref "B1") (pin "26") (pinfunction "26_26") (pintype "bidirectional"))
    )
    (net (code "65") (name "unconnected-(MIDI_INA-KL-Pad1)") (class "Default")
      (node (ref "MIDI_IN") (pin "1") (pinfunction "KL_1") (pintype "passive"))
    )
  )
)
